# Analog_Sensors.net
KiCad netlist of a schematic drawn in Altium Designer
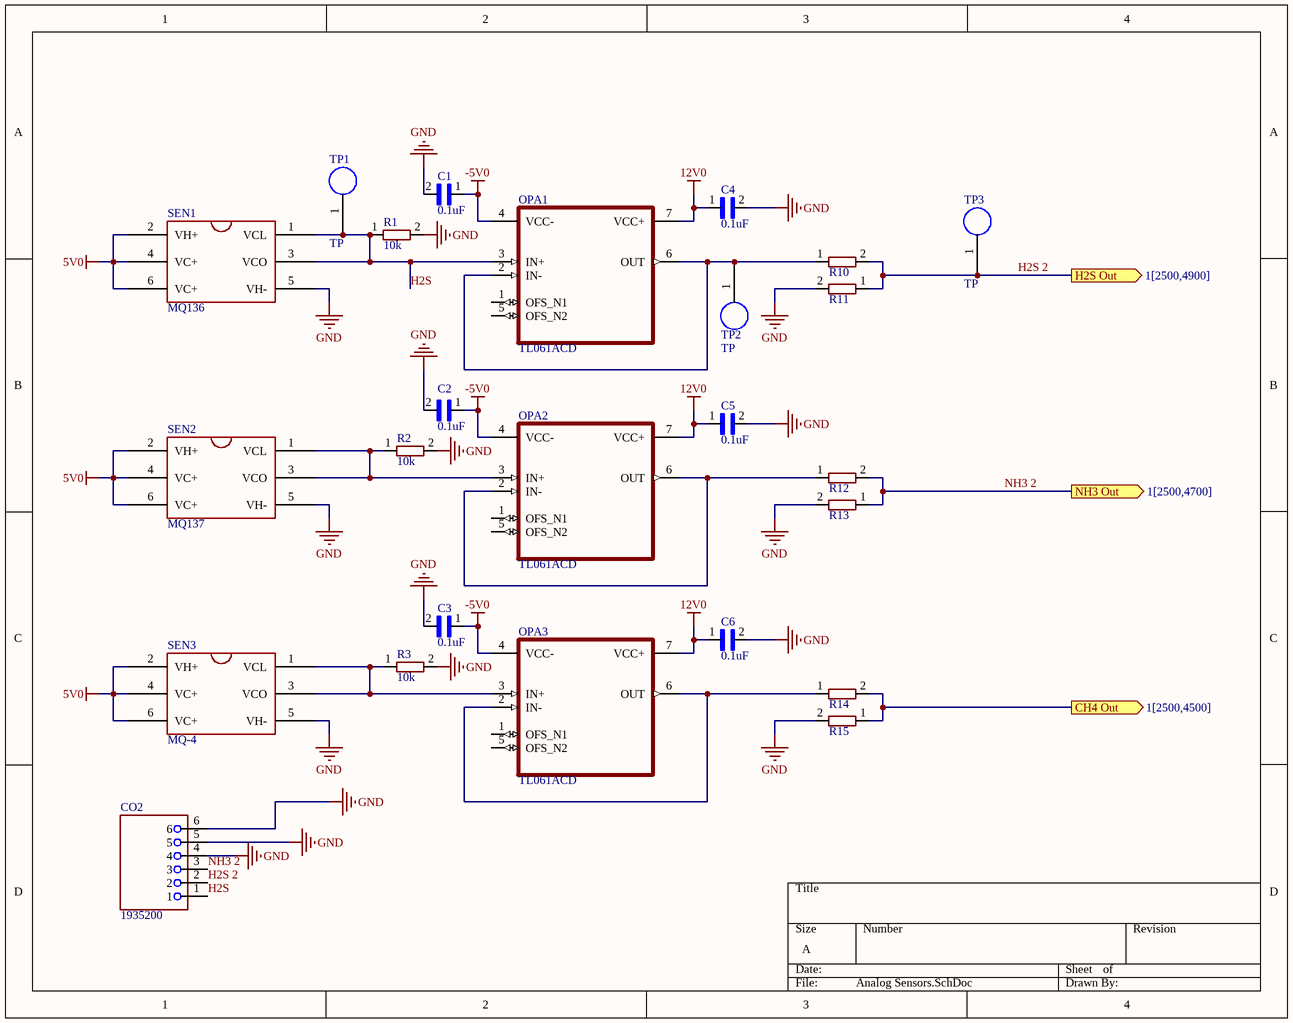
[diagram p0: Analog Sensors.SchDoc]

(export (version "E")
  (design (tool "Eeschema 10.0.6"))
  (components
    (comp (ref "C1")
      (value "0.1uF")
      (footprint "0.1uF Capacitor")
      (description "No Description Available")
      (libsource (lib "0.1uF Capacitor") (part "CC1206JRX7R9BB104"))
    )
    (comp (ref "C2")
      (value "0.1uF")
      (footprint "0.1uF Capacitor")
      (description "No Description Available")
      (libsource (lib "0.1uF Capacitor") (part "CC1206JRX7R9BB104"))
    )
    (comp (ref "C3")
      (value "0.1uF")
      (footprint "0.1uF Capacitor")
      (description "No Description Available")
      (libsource (lib "0.1uF Capacitor") (part "CC1206JRX7R9BB104"))
    )
    (comp (ref "C4")
      (value "0.1uF")
      (footprint "0.1uF Capacitor")
      (description "No Description Available")
      (libsource (lib "") (part "CC1206JRX7R9BB104_1"))
    )
    (comp (ref "C5")
      (value "0.1uF")
      (footprint "0.1uF Capacitor")
      (description "No Description Available")
      (libsource (lib "") (part "CC1206JRX7R9BB104_1"))
    )
    (comp (ref "C6")
      (value "0.1uF")
      (footprint "0.1uF Capacitor")
      (description "No Description Available")
      (libsource (lib "") (part "CC1206JRX7R9BB104_1"))
    )
    (comp (ref "CO2")
      (value "1935200")
      (footprint "PHOENIX_1935200")
      (fields (field (name "MF") "Littelfuse"))
      (libsource (lib "Main Connector") (part "1935200"))
    )
    (comp (ref "OPA1")
      (value "TL061ACD")
      (footprint "TL061ACD:SOIC127P599X175-8N")
      (libsource (lib "TL061ACD") (part "TL061ACD"))
    )
    (comp (ref "OPA2")
      (value "TL061ACD")
      (footprint "TL061ACD:SOIC127P599X175-8N")
      (libsource (lib "TL061ACD") (part "TL061ACD"))
    )
    (comp (ref "OPA3")
      (value "TL061ACD")
      (footprint "TL061ACD:SOIC127P599X175-8N")
      (libsource (lib "TL061ACD") (part "TL061ACD"))
    )
    (comp (ref "R1")
      (value "10k")
      (footprint "10K Resistor:0603")
      (description "http://octopart.com/rc0603fr-1310kl-yageo+%2F+phycomp-25905087")
      (fields (field (name "MP") "RC0603FR-1310KL"))
      (libsource (lib "") (part "RC0603FR-1310KL_1"))
    )
    (comp (ref "R2")
      (value "10k")
      (footprint "10K Resistor:0603")
      (description "http://octopart.com/rc0603fr-1310kl-yageo+%2F+phycomp-25905087")
      (fields (field (name "MP") "RC0603FR-1310KL"))
      (libsource (lib "") (part "RC0603FR-1310KL_1"))
    )
    (comp (ref "R3")
      (value "10k")
      (footprint "10K Resistor:0603")
      (description "http://octopart.com/rc0603fr-1310kl-yageo+%2F+phycomp-25905087")
      (fields (field (name "MP") "RC0603FR-1310KL"))
      (libsource (lib "") (part "RC0603FR-1310KL_1"))
    )
    (comp (ref "R10")
      (value "RC0603FR-1310KL")
      (footprint "10K Resistor:0603")
      (description "http://octopart.com/rc0603fr-1310kl-yageo+%2F+phycomp-25905087")
      (libsource (lib "") (part "RC0603FR-1310KL_1"))
    )
    (comp (ref "R11")
      (value "RC0603FR-1310KL")
      (footprint "10K Resistor:0603")
      (description "http://octopart.com/rc0603fr-1310kl-yageo+%2F+phycomp-25905087")
      (libsource (lib "10K Resistor") (part "RC0603FR-1310KL"))
    )
    (comp (ref "R12")
      (value "RC0603FR-1310KL")
      (footprint "10K Resistor:0603")
      (description "http://octopart.com/rc0603fr-1310kl-yageo+%2F+phycomp-25905087")
      (libsource (lib "") (part "RC0603FR-1310KL_1"))
    )
    (comp (ref "R13")
      (value "RC0603FR-1310KL")
      (footprint "10K Resistor:0603")
      (description "http://octopart.com/rc0603fr-1310kl-yageo+%2F+phycomp-25905087")
      (libsource (lib "10K Resistor") (part "RC0603FR-1310KL"))
    )
    (comp (ref "R14")
      (value "RC0603FR-1310KL")
      (footprint "10K Resistor:0603")
      (description "http://octopart.com/rc0603fr-1310kl-yageo+%2F+phycomp-25905087")
      (libsource (lib "") (part "RC0603FR-1310KL_1"))
    )
    (comp (ref "R15")
      (value "RC0603FR-1310KL")
      (footprint "10K Resistor:0603")
      (description "http://octopart.com/rc0603fr-1310kl-yageo+%2F+phycomp-25905087")
      (libsource (lib "10K Resistor") (part "RC0603FR-1310KL"))
    )
    (comp (ref "SEN1")
      (value "MQ136")
      (footprint "MQ136")
      (description "Hydrogen Sulfide Sensor")
      (libsource (lib "MQ136") (part "MQ136"))
    )
    (comp (ref "SEN2")
      (value "MQ137")
      (footprint "MQ137")
      (description "Ammonia Sensor")
      (libsource (lib "MQ137") (part "MQ137"))
    )
    (comp (ref "SEN3")
      (value "MQ-4")
      (footprint "MQ4")
      (description "Methane Sensor")
      (libsource (lib "MQ-4") (part "MQ-4"))
    )
    (comp (ref "TP1")
      (value "TP")
      (footprint "TestPoint")
      (description "Test point for voltage, current, ect.")
      (libsource (lib "TestPoint") (part "TestPoint"))
    )
    (comp (ref "TP2")
      (value "TP")
      (footprint "TestPoint")
      (description "Test point for voltage, current, ect.")
      (libsource (lib "TestPoint") (part "TestPoint"))
    )
    (comp (ref "TP3")
      (value "TP")
      (footprint "TestPoint")
      (description "Test point for voltage, current, ect.")
      (libsource (lib "TestPoint") (part "TestPoint"))
    )
  )
  (nets
    (net (code "1") (name "-5V0") (class "Default")
      (node (ref "C1") (pin "1") (pintype "passive"))
      (node (ref "C2") (pin "1") (pintype "passive"))
      (node (ref "C3") (pin "1") (pintype "passive"))
      (node (ref "OPA1") (pin "4") (pinfunction "VCC-_4") (pintype "power_in"))
      (node (ref "OPA2") (pin "4") (pinfunction "VCC-_4") (pintype "power_in"))
      (node (ref "OPA3") (pin "4") (pinfunction "VCC-_4") (pintype "power_in"))
    )
    (net (code "2") (name "/CH4 Out") (class "Default")
      (node (ref "R14") (pin "2") (pintype "passive"))
      (node (ref "R15") (pin "1") (pintype "passive"))
    )
    (net (code "3") (name "/H2S") (class "Default")
      (node (ref "CO2") (pin "1") (pinfunction "1_1") (pintype "passive"))
      (node (ref "OPA1") (pin "3") (pinfunction "IN+_3") (pintype "input"))
      (node (ref "R1") (pin "1") (pintype "passive"))
      (node (ref "SEN1") (pin "1") (pinfunction "VCL_1") (pintype "passive"))
      (node (ref "SEN1") (pin "3") (pinfunction "VCO_3") (pintype "passive"))
      (node (ref "TP1") (pin "1") (pintype "passive"))
    )
    (net (code "4") (name "/H2S 2") (class "Default")
      (node (ref "CO2") (pin "2") (pinfunction "2_2") (pintype "passive"))
      (node (ref "R10") (pin "2") (pintype "passive"))
      (node (ref "R11") (pin "1") (pintype "passive"))
      (node (ref "TP3") (pin "1") (pintype "passive"))
    )
    (net (code "5") (name "/NH3 2") (class "Default")
      (node (ref "CO2") (pin "3") (pinfunction "3_3") (pintype "passive"))
      (node (ref "R12") (pin "2") (pintype "passive"))
      (node (ref "R13") (pin "1") (pintype "passive"))
    )
    (net (code "6") (name "5V0") (class "Default")
      (node (ref "SEN1") (pin "2") (pinfunction "VH+_2") (pintype "passive"))
      (node (ref "SEN1") (pin "4") (pinfunction "VC+_4") (pintype "passive"))
      (node (ref "SEN1") (pin "6") (pinfunction "VC+_6") (pintype "passive"))
      (node (ref "SEN2") (pin "2") (pinfunction "VH+_2") (pintype "passive"))
      (node (ref "SEN2") (pin "4") (pinfunction "VC+_4") (pintype "passive"))
      (node (ref "SEN2") (pin "6") (pinfunction "VC+_6") (pintype "passive"))
      (node (ref "SEN3") (pin "2") (pinfunction "VH+_2") (pintype "passive"))
      (node (ref "SEN3") (pin "4") (pinfunction "VC+_4") (pintype "passive"))
      (node (ref "SEN3") (pin "6") (pinfunction "VC+_6") (pintype "passive"))
    )
    (net (code "7") (name "12V0") (class "Default")
      (node (ref "C4") (pin "1") (pintype "passive"))
      (node (ref "C5") (pin "1") (pintype "passive"))
      (node (ref "C6") (pin "1") (pintype "passive"))
      (node (ref "OPA1") (pin "7") (pinfunction "VCC+_7") (pintype "power_in"))
      (node (ref "OPA2") (pin "7") (pinfunction "VCC+_7") (pintype "power_in"))
      (node (ref "OPA3") (pin "7") (pinfunction "VCC+_7") (pintype "power_in"))
    )
    (net (code "8") (name "GND") (class "Default")
      (node (ref "C1") (pin "2") (pintype "passive"))
      (node (ref "C2") (pin "2") (pintype "passive"))
      (node (ref "C3") (pin "2") (pintype "passive"))
      (node (ref "C4") (pin "2") (pintype "passive"))
      (node (ref "C5") (pin "2") (pintype "passive"))
      (node (ref "C6") (pin "2") (pintype "passive"))
      (node (ref "CO2") (pin "4") (pinfunction "4_4") (pintype "passive"))
      (node (ref "CO2") (pin "5") (pinfunction "5_5") (pintype "passive"))
      (node (ref "CO2") (pin "6") (pinfunction "6_6") (pintype "passive"))
      (node (ref "R1") (pin "2") (pintype "passive"))
      (node (ref "R11") (pin "2") (pintype "passive"))
      (node (ref "R13") (pin "2") (pintype "passive"))
      (node (ref "R15") (pin "2") (pintype "passive"))
      (node (ref "R2") (pin "2") (pintype "passive"))
      (node (ref "R3") (pin "2") (pintype "passive"))
      (node (ref "SEN1") (pin "5") (pinfunction "VH-_5") (pintype "passive"))
      (node (ref "SEN2") (pin "5") (pinfunction "VH-_5") (pintype "passive"))
      (node (ref "SEN3") (pin "5") (pinfunction "VH-_5") (pintype "passive"))
    )
    (net (code "9") (name "Net-(OPA1-IN-)") (class "Default")
      (node (ref "OPA1") (pin "2") (pinfunction "IN-_2") (pintype "input"))
      (node (ref "OPA1") (pin "6") (pinfunction "OUT_6") (pintype "output"))
      (node (ref "R10") (pin "1") (pintype "passive"))
      (node (ref "TP2") (pin "1") (pintype "passive"))
    )
    (net (code "10") (name "Net-(OPA2-IN+)") (class "Default")
      (node (ref "OPA2") (pin "3") (pinfunction "IN+_3") (pintype "input"))
      (node (ref "R2") (pin "1") (pintype "passive"))
      (node (ref "SEN2") (pin "1") (pinfunction "VCL_1") (pintype "passive"))
      (node (ref "SEN2") (pin "3") (pinfunction "VCO_3") (pintype "passive"))
    )
    (net (code "11") (name "Net-(OPA2-IN-)") (class "Default")
      (node (ref "OPA2") (pin "2") (pinfunction "IN-_2") (pintype "input"))
      (node (ref "OPA2") (pin "6") (pinfunction "OUT_6") (pintype "output"))
      (node (ref "R12") (pin "1") (pintype "passive"))
    )
    (net (code "12") (name "Net-(OPA3-IN+)") (class "Default")
      (node (ref "OPA3") (pin "3") (pinfunction "IN+_3") (pintype "input"))
      (node (ref "R3") (pin "1") (pintype "passive"))
      (node (ref "SEN3") (pin "1") (pinfunction "VCL_1") (pintype "passive"))
      (node (ref "SEN3") (pin "3") (pinfunction "VCO_3") (pintype "passive"))
    )
    (net (code "13") (name "Net-(OPA3-IN-)") (class "Default")
      (node (ref "OPA3") (pin "2") (pinfunction "IN-_2") (pintype "input"))
      (node (ref "OPA3") (pin "6") (pinfunction "OUT_6") (pintype "output"))
      (node (ref "R14") (pin "1") (pintype "passive"))
    )
    (net (code "14") (name "unconnected-(OPA1-OFS_N1-Pad1)") (class "Default")
      (node (ref "OPA1") (pin "1") (pinfunction "OFS_N1_1") (pintype "bidirectional"))
    )
    (net (code "15") (name "unconnected-(OPA1-OFS_N2-Pad5)") (class "Default")
      (node (ref "OPA1") (pin "5") (pinfunction "OFS_N2_5") (pintype "bidirectional"))
    )
    (net (code "16") (name "unconnected-(OPA2-OFS_N1-Pad1)") (class "Default")
      (node (ref "OPA2") (pin "1") (pinfunction "OFS_N1_1") (pintype "bidirectional"))
    )
    (net (code "17") (name "unconnected-(OPA2-OFS_N2-Pad5)") (class "Default")
      (node (ref "OPA2") (pin "5") (pinfunction "OFS_N2_5") (pintype "bidirectional"))
    )
    (net (code "18") (name "unconnected-(OPA3-OFS_N1-Pad1)") (class "Default")
      (node (ref "OPA3") (pin "1") (pinfunction "OFS_N1_1") (pintype "bidirectional"))
    )
    (net (code "19") (name "unconnected-(OPA3-OFS_N2-Pad5)") (class "Default")
      (node (ref "OPA3") (pin "5") (pinfunction "OFS_N2_5") (pintype "bidirectional"))
    )
  )
)
